# TUN7_Control.net
KiCad netlist of a schematic drawn in Altium Designer
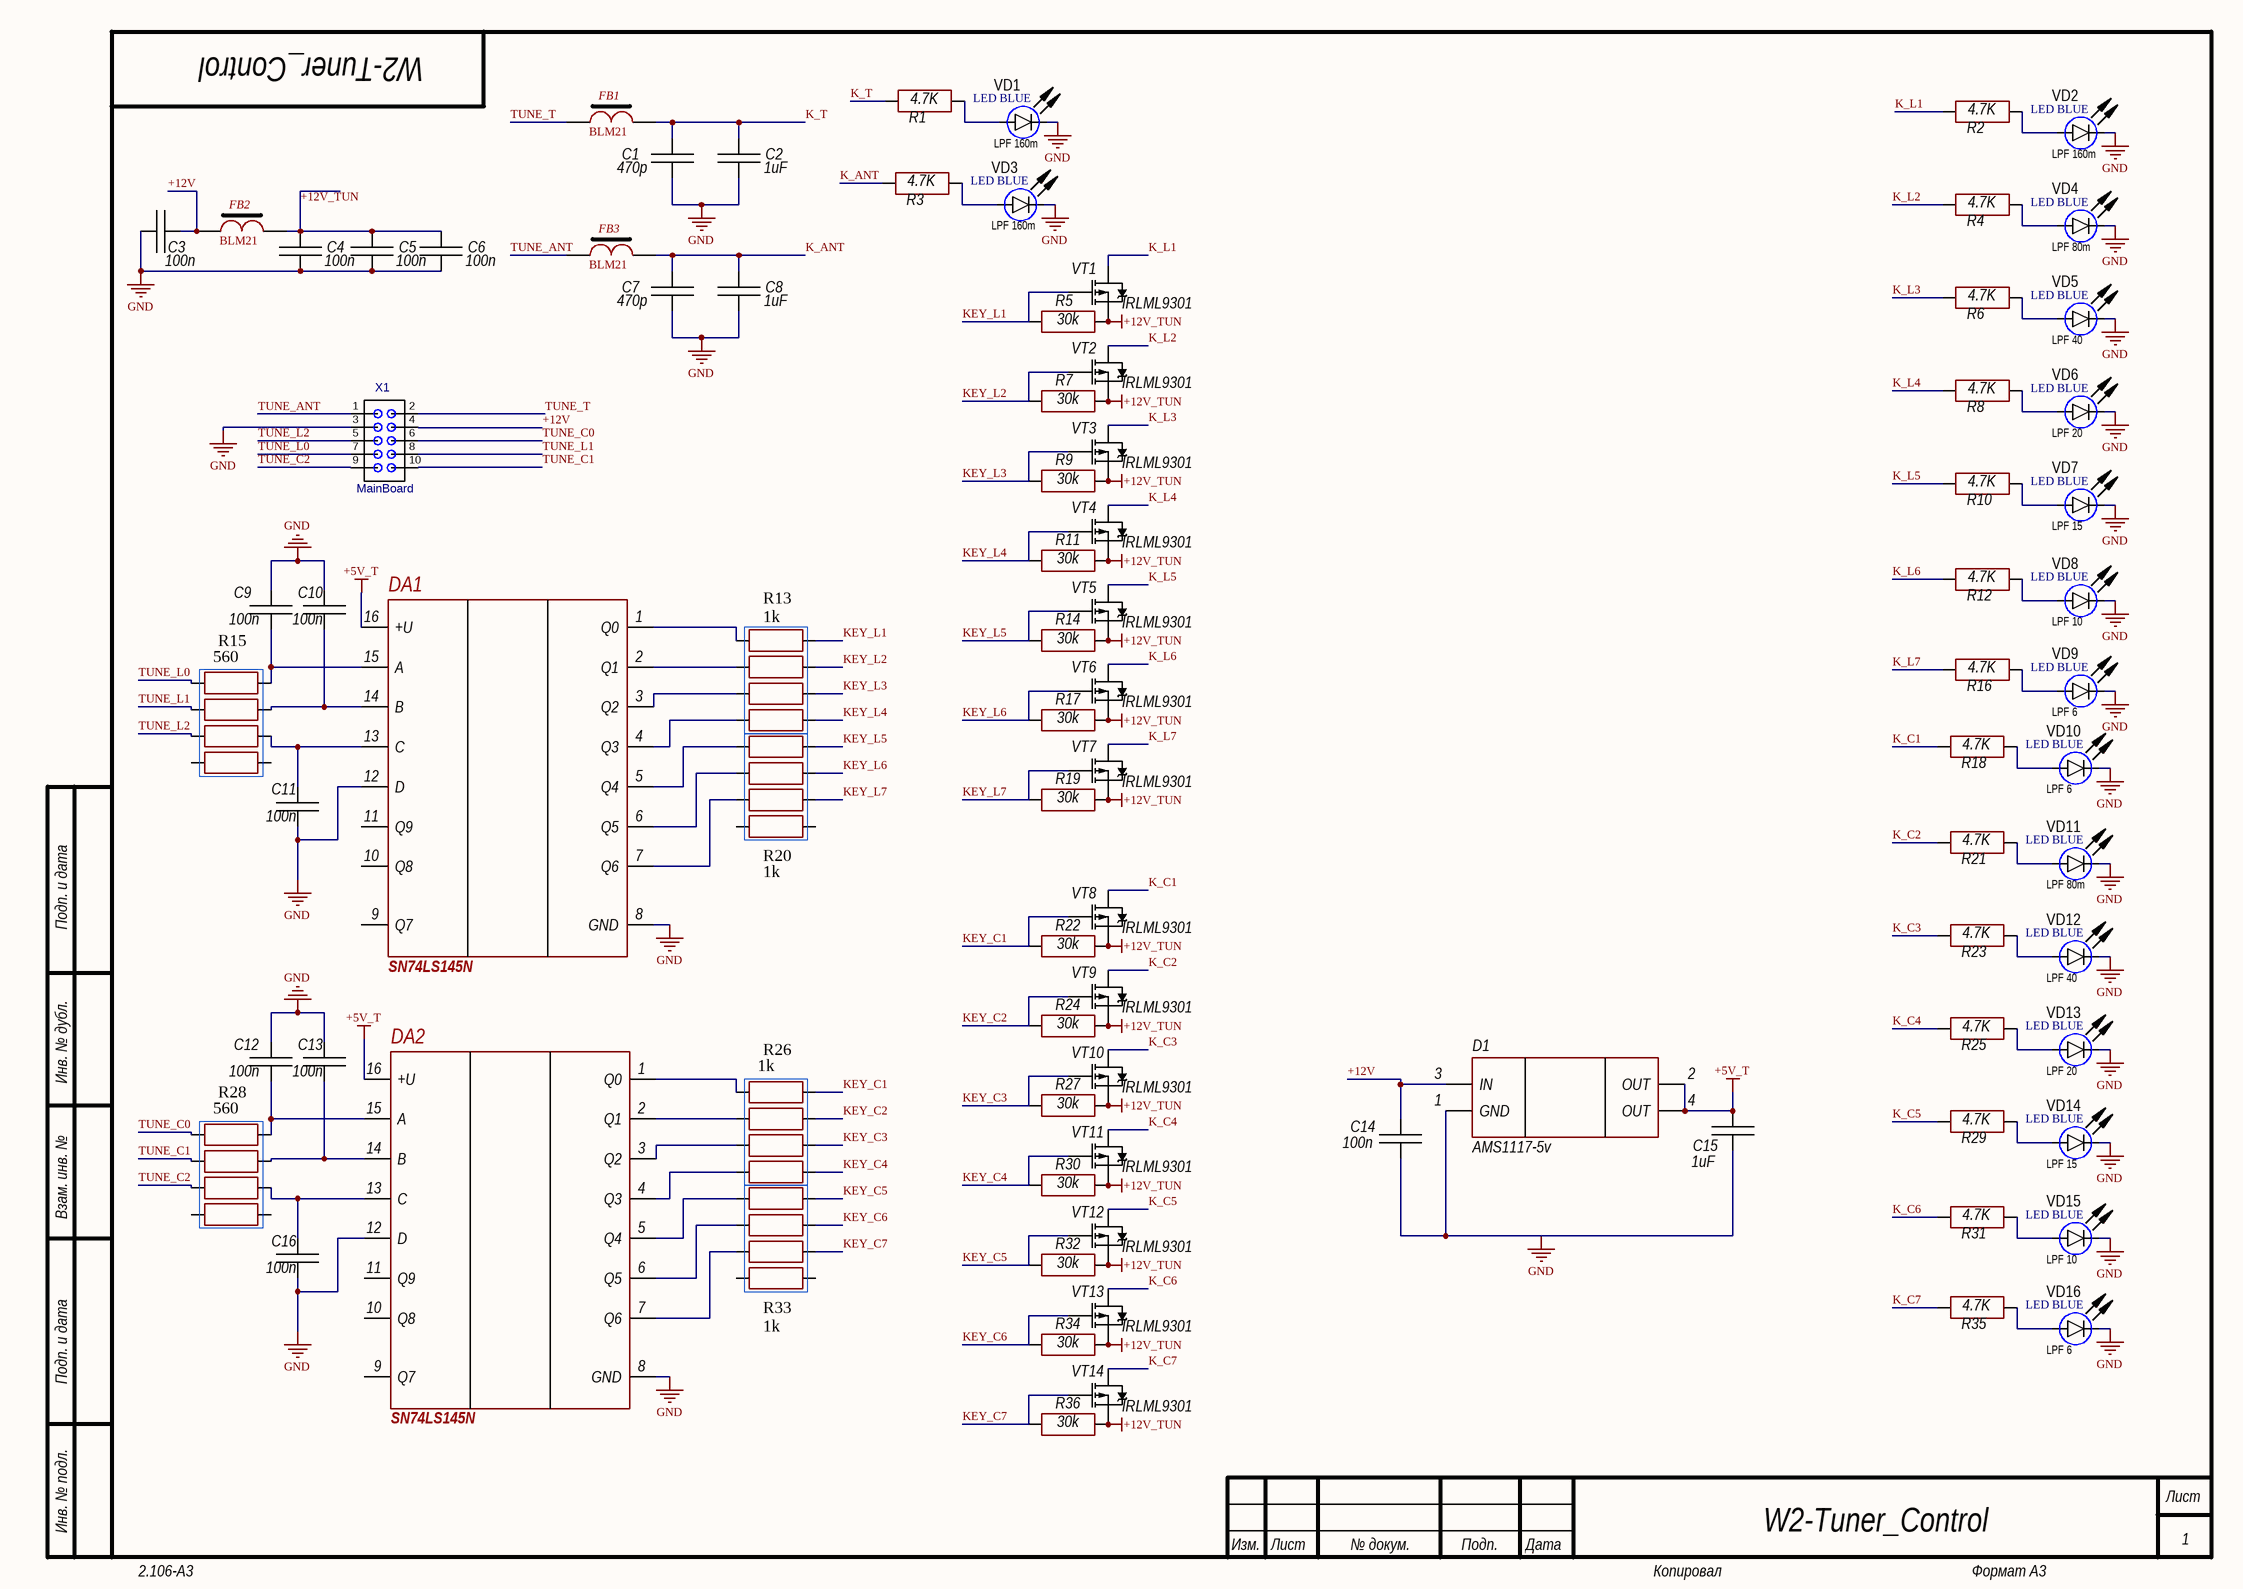
[diagram p0: TUN7_Control.SchDoc]

(export (version "E")
  (design (tool "Eeschema 10.0.6"))
  (components
    (comp (ref "C1")
      (value "470p")
      (footprint "standard:CH0805C")
      (libsource (lib "Discrete") (part "Capacitor"))
    )
    (comp (ref "C2")
      (value "1uF")
      (footprint "standard:CH0805C")
      (libsource (lib "Discrete") (part "Capacitor"))
    )
    (comp (ref "C3")
      (value "100n")
      (footprint "standard:CH0805C")
      (libsource (lib "Discrete") (part "Capacitor"))
    )
    (comp (ref "C4")
      (value "100n")
      (footprint "standard:CH0805C")
      (libsource (lib "Discrete") (part "Capacitor"))
    )
    (comp (ref "C5") (value "100n") (footprint "standard:CH0805C") (libsource (lib "") (part "Capacitor_1")))
    (comp (ref "C6") (value "100n") (footprint "standard:CH0805C") (libsource (lib "") (part "Capacitor_1")))
    (comp (ref "C7")
      (value "470p")
      (footprint "standard:CH0805C")
      (libsource (lib "Discrete") (part "Capacitor"))
    )
    (comp (ref "C8")
      (value "1uF")
      (footprint "standard:CH0805C")
      (libsource (lib "Discrete") (part "Capacitor"))
    )
    (comp (ref "C9")
      (value "100n")
      (footprint "standard:CH0805C")
      (libsource (lib "Discrete") (part "Capacitor"))
    )
    (comp (ref "C10")
      (value "100n")
      (footprint "standard:CH0805C")
      (libsource (lib "Discrete") (part "Capacitor"))
    )
    (comp (ref "C11")
      (value "100n")
      (footprint "standard:CH0805C")
      (libsource (lib "Discrete") (part "Capacitor"))
    )
    (comp (ref "C12")
      (value "100n")
      (footprint "standard:CH0805C")
      (libsource (lib "Discrete") (part "Capacitor"))
    )
    (comp (ref "C13")
      (value "100n")
      (footprint "standard:CH0805C")
      (libsource (lib "Discrete") (part "Capacitor"))
    )
    (comp (ref "C14")
      (value "100n")
      (footprint "standard:CH0805C")
      (libsource (lib "Discrete") (part "Capacitor"))
    )
    (comp (ref "C15")
      (value "1uF")
      (footprint "standard:CH0805C")
      (libsource (lib "Discrete") (part "Capacitor"))
    )
    (comp (ref "C16")
      (value "100n")
      (footprint "standard:CH0805C")
      (libsource (lib "Discrete") (part "Capacitor"))
    )
    (comp (ref "D1")
      (value "AMS1117-5v")
      (footprint "standard:SOT223")
      (description "LDO")
      (fields (field (name "MANUFACTURER") "ON Semiconductor"))
      (libsource (lib "Power Supplies") (part "NCP1117LPST50T3G"))
    )
    (comp (ref "DA1")
      (value "SN74LS145N")
      (footprint "16-SOP")
      (libsource (lib "Digital") (part "SN74LS145N"))
    )
    (comp (ref "DA2") (value "SN74LS145N") (footprint "16-SOP") (libsource (lib "") (part "SN74LS145N_1")))
    (comp (ref "FB1") (value "BLM21") (footprint "CH0805L") (libsource (lib "Discrete") (part "FB-1")))
    (comp (ref "FB2") (value "BLM21") (footprint "CH0805L") (libsource (lib "Discrete") (part "FB-1")))
    (comp (ref "FB3") (value "BLM21") (footprint "CH0805L") (libsource (lib "Discrete") (part "FB-1")))
    (comp (ref "R1")
      (value "4.7K")
      (footprint "standard:CH0805R")
      (libsource (lib "Discrete") (part "Resistor"))
    )
    (comp (ref "R2")
      (value "4.7K")
      (footprint "standard:CH0805R")
      (libsource (lib "Discrete") (part "Resistor"))
    )
    (comp (ref "R3")
      (value "4.7K")
      (footprint "standard:CH0805R")
      (libsource (lib "Discrete") (part "Resistor"))
    )
    (comp (ref "R4")
      (value "4.7K")
      (footprint "standard:CH0805R")
      (libsource (lib "Discrete") (part "Resistor"))
    )
    (comp (ref "R5")
      (value "30k")
      (footprint "standard:CH0805R")
      (libsource (lib "Discrete") (part "Resistor"))
    )
    (comp (ref "R6")
      (value "4.7K")
      (footprint "standard:CH0805R")
      (libsource (lib "Discrete") (part "Resistor"))
    )
    (comp (ref "R7")
      (value "30k")
      (footprint "standard:CH0805R")
      (libsource (lib "Discrete") (part "Resistor"))
    )
    (comp (ref "R8")
      (value "4.7K")
      (footprint "standard:CH0805R")
      (libsource (lib "Discrete") (part "Resistor"))
    )
    (comp (ref "R9")
      (value "30k")
      (footprint "standard:CH0805R")
      (libsource (lib "Discrete") (part "Resistor"))
    )
    (comp (ref "R10")
      (value "4.7K")
      (footprint "standard:CH0805R")
      (libsource (lib "Discrete") (part "Resistor"))
    )
    (comp (ref "R11")
      (value "30k")
      (footprint "standard:CH0805R")
      (libsource (lib "Discrete") (part "Resistor"))
    )
    (comp (ref "R12")
      (value "4.7K")
      (footprint "standard:CH0805R")
      (libsource (lib "Discrete") (part "Resistor"))
    )
    (comp (ref "R13") (value "1k") (footprint "CAT16") (libsource (lib "Discrete") (part "CAT10-0804")))
    (comp (ref "R14")
      (value "30k")
      (footprint "standard:CH0805R")
      (libsource (lib "Discrete") (part "Resistor"))
    )
    (comp (ref "R15") (value "560") (footprint "CAT16") (libsource (lib "Discrete") (part "CAT10-0804")))
    (comp (ref "R16")
      (value "4.7K")
      (footprint "standard:CH0805R")
      (libsource (lib "Discrete") (part "Resistor"))
    )
    (comp (ref "R17")
      (value "30k")
      (footprint "standard:CH0805R")
      (libsource (lib "Discrete") (part "Resistor"))
    )
    (comp (ref "R18")
      (value "4.7K")
      (footprint "standard:CH0805R")
      (libsource (lib "Discrete") (part "Resistor"))
    )
    (comp (ref "R19")
      (value "30k")
      (footprint "standard:CH0805R")
      (libsource (lib "Discrete") (part "Resistor"))
    )
    (comp (ref "R20") (value "1k") (footprint "CAT16") (libsource (lib "Discrete") (part "CAT10-0804")))
    (comp (ref "R21")
      (value "4.7K")
      (footprint "standard:CH0805R")
      (libsource (lib "Discrete") (part "Resistor"))
    )
    (comp (ref "R22")
      (value "30k")
      (footprint "standard:CH0805R")
      (libsource (lib "Discrete") (part "Resistor"))
    )
    (comp (ref "R23")
      (value "4.7K")
      (footprint "standard:CH0805R")
      (libsource (lib "Discrete") (part "Resistor"))
    )
    (comp (ref "R24")
      (value "30k")
      (footprint "standard:CH0805R")
      (libsource (lib "Discrete") (part "Resistor"))
    )
    (comp (ref "R25")
      (value "4.7K")
      (footprint "standard:CH0805R")
      (libsource (lib "Discrete") (part "Resistor"))
    )
    (comp (ref "R26") (value "1k") (footprint "CAT16") (libsource (lib "Discrete") (part "CAT10-0804")))
    (comp (ref "R27")
      (value "30k")
      (footprint "standard:CH0805R")
      (libsource (lib "Discrete") (part "Resistor"))
    )
    (comp (ref "R28") (value "560") (footprint "CAT16") (libsource (lib "Discrete") (part "CAT10-0804")))
    (comp (ref "R29")
      (value "4.7K")
      (footprint "standard:CH0805R")
      (libsource (lib "Discrete") (part "Resistor"))
    )
    (comp (ref "R30")
      (value "30k")
      (footprint "standard:CH0805R")
      (libsource (lib "Discrete") (part "Resistor"))
    )
    (comp (ref "R31")
      (value "4.7K")
      (footprint "standard:CH0805R")
      (libsource (lib "Discrete") (part "Resistor"))
    )
    (comp (ref "R32")
      (value "30k")
      (footprint "standard:CH0805R")
      (libsource (lib "Discrete") (part "Resistor"))
    )
    (comp (ref "R33") (value "1k") (footprint "CAT16") (libsource (lib "Discrete") (part "CAT10-0804")))
    (comp (ref "R34")
      (value "30k")
      (footprint "standard:CH0805R")
      (libsource (lib "Discrete") (part "Resistor"))
    )
    (comp (ref "R35")
      (value "4.7K")
      (footprint "standard:CH0805R")
      (libsource (lib "Discrete") (part "Resistor"))
    )
    (comp (ref "R36")
      (value "30k")
      (footprint "standard:CH0805R")
      (libsource (lib "Discrete") (part "Resistor"))
    )
    (comp (ref "VD1")
      (value "LED BLUE")
      (footprint "StandardCase:LED: 0805B")
      (fields
        (field (name "VALUEMANUFACTURERPARTNUMBER") "LED, *, *, *, -55...+150°C")
        (field (name "COLOR") "LPF 160m")
      )
      (libsource (lib "Diode") (part "LED_single"))
    )
    (comp (ref "VD2")
      (value "LED BLUE")
      (footprint "StandardCase:LED: 0805B")
      (fields
        (field (name "VALUEMANUFACTURERPARTNUMBER") "LED, *, *, *, -55...+150°C")
        (field (name "COLOR") "LPF 160m")
      )
      (libsource (lib "Diode") (part "LED_single"))
    )
    (comp (ref "VD3")
      (value "LED BLUE")
      (footprint "StandardCase:LED: 0805B")
      (fields
        (field (name "VALUEMANUFACTURERPARTNUMBER") "LED, *, *, *, -55...+150°C")
        (field (name "COLOR") "LPF 160m")
      )
      (libsource (lib "Diode") (part "LED_single"))
    )
    (comp (ref "VD4")
      (value "LED BLUE")
      (footprint "StandardCase:LED: 0805B")
      (fields
        (field (name "VALUEMANUFACTURERPARTNUMBER") "LED, *, *, *, -55...+150°C")
        (field (name "COLOR") "LPF 80m")
      )
      (libsource (lib "Diode") (part "LED_single"))
    )
    (comp (ref "VD5")
      (value "LED BLUE")
      (footprint "StandardCase:LED: 0805B")
      (fields
        (field (name "VALUEMANUFACTURERPARTNUMBER") "LED, *, *, *, -55...+150°C")
        (field (name "COLOR") "LPF 40")
      )
      (libsource (lib "Diode") (part "LED_single"))
    )
    (comp (ref "VD6")
      (value "LED BLUE")
      (footprint "StandardCase:LED: 0805B")
      (fields
        (field (name "VALUEMANUFACTURERPARTNUMBER") "LED, *, *, *, -55...+150°C")
        (field (name "COLOR") "LPF 20")
      )
      (libsource (lib "Diode") (part "LED_single"))
    )
    (comp (ref "VD7")
      (value "LED BLUE")
      (footprint "StandardCase:LED: 0805B")
      (fields
        (field (name "VALUEMANUFACTURERPARTNUMBER") "LED, *, *, *, -55...+150°C")
        (field (name "COLOR") "LPF 15")
      )
      (libsource (lib "Diode") (part "LED_single"))
    )
    (comp (ref "VD8")
      (value "LED BLUE")
      (footprint "StandardCase:LED: 0805B")
      (fields
        (field (name "VALUEMANUFACTURERPARTNUMBER") "LED, *, *, *, -55...+150°C")
        (field (name "COLOR") "LPF 10")
      )
      (libsource (lib "Diode") (part "LED_single"))
    )
    (comp (ref "VD9")
      (value "LED BLUE")
      (footprint "StandardCase:LED: 0805B")
      (fields
        (field (name "VALUEMANUFACTURERPARTNUMBER") "LED, *, *, *, -55...+150°C")
        (field (name "COLOR") "LPF 6")
      )
      (libsource (lib "Diode") (part "LED_single"))
    )
    (comp (ref "VD10")
      (value "LED BLUE")
      (footprint "StandardCase:LED: 0805B")
      (fields
        (field (name "VALUEMANUFACTURERPARTNUMBER") "LED, *, *, *, -55...+150°C")
        (field (name "COLOR") "LPF 6")
      )
      (libsource (lib "Diode") (part "LED_single"))
    )
    (comp (ref "VD11")
      (value "LED BLUE")
      (footprint "StandardCase:LED: 0805B")
      (fields
        (field (name "VALUEMANUFACTURERPARTNUMBER") "LED, *, *, *, -55...+150°C")
        (field (name "COLOR") "LPF 80m")
      )
      (libsource (lib "Diode") (part "LED_single"))
    )
    (comp (ref "VD12")
      (value "LED BLUE")
      (footprint "StandardCase:LED: 0805B")
      (fields
        (field (name "VALUEMANUFACTURERPARTNUMBER") "LED, *, *, *, -55...+150°C")
        (field (name "COLOR") "LPF 40")
      )
      (libsource (lib "Diode") (part "LED_single"))
    )
    (comp (ref "VD13")
      (value "LED BLUE")
      (footprint "StandardCase:LED: 0805B")
      (fields
        (field (name "VALUEMANUFACTURERPARTNUMBER") "LED, *, *, *, -55...+150°C")
        (field (name "COLOR") "LPF 20")
      )
      (libsource (lib "Diode") (part "LED_single"))
    )
    (comp (ref "VD14")
      (value "LED BLUE")
      (footprint "StandardCase:LED: 0805B")
      (fields
        (field (name "VALUEMANUFACTURERPARTNUMBER") "LED, *, *, *, -55...+150°C")
        (field (name "COLOR") "LPF 15")
      )
      (libsource (lib "Diode") (part "LED_single"))
    )
    (comp (ref "VD15")
      (value "LED BLUE")
      (footprint "StandardCase:LED: 0805B")
      (fields
        (field (name "VALUEMANUFACTURERPARTNUMBER") "LED, *, *, *, -55...+150°C")
        (field (name "COLOR") "LPF 10")
      )
      (libsource (lib "Diode") (part "LED_single"))
    )
    (comp (ref "VD16")
      (value "LED BLUE")
      (footprint "StandardCase:LED: 0805B")
      (fields
        (field (name "VALUEMANUFACTURERPARTNUMBER") "LED, *, *, *, -55...+150°C")
        (field (name "COLOR") "LPF 6")
      )
      (libsource (lib "Diode") (part "LED_single"))
    )
    (comp (ref "VT1")
      (value "IRLML9301")
      (footprint "standard:SOT23_132")
      (description "Mosfet")
      (libsource (lib "Transistor") (part "IRLML9301"))
    )
    (comp (ref "VT2")
      (value "IRLML9301")
      (footprint "standard:SOT23_132")
      (description "Mosfet")
      (libsource (lib "Transistor") (part "IRLML9301"))
    )
    (comp (ref "VT3")
      (value "IRLML9301")
      (footprint "standard:SOT23_132")
      (description "Mosfet")
      (libsource (lib "Transistor") (part "IRLML9301"))
    )
    (comp (ref "VT4")
      (value "IRLML9301")
      (footprint "standard:SOT23_132")
      (description "Mosfet")
      (libsource (lib "Transistor") (part "IRLML9301"))
    )
    (comp (ref "VT5")
      (value "IRLML9301")
      (footprint "standard:SOT23_132")
      (description "Mosfet")
      (libsource (lib "Transistor") (part "IRLML9301"))
    )
    (comp (ref "VT6")
      (value "IRLML9301")
      (footprint "standard:SOT23_132")
      (description "Mosfet")
      (libsource (lib "Transistor") (part "IRLML9301"))
    )
    (comp (ref "VT7")
      (value "IRLML9301")
      (footprint "standard:SOT23_132")
      (description "Mosfet")
      (libsource (lib "Transistor") (part "IRLML9301"))
    )
    (comp (ref "VT8")
      (value "IRLML9301")
      (footprint "standard:SOT23_132")
      (description "Mosfet")
      (libsource (lib "Transistor") (part "IRLML9301"))
    )
    (comp (ref "VT9")
      (value "IRLML9301")
      (footprint "standard:SOT23_132")
      (description "Mosfet")
      (libsource (lib "Transistor") (part "IRLML9301"))
    )
    (comp (ref "VT10")
      (value "IRLML9301")
      (footprint "standard:SOT23_132")
      (description "Mosfet")
      (libsource (lib "Transistor") (part "IRLML9301"))
    )
    (comp (ref "VT11")
      (value "IRLML9301")
      (footprint "standard:SOT23_132")
      (description "Mosfet")
      (libsource (lib "Transistor") (part "IRLML9301"))
    )
    (comp (ref "VT12")
      (value "IRLML9301")
      (footprint "standard:SOT23_132")
      (description "Mosfet")
      (libsource (lib "Transistor") (part "IRLML9301"))
    )
    (comp (ref "VT13")
      (value "IRLML9301")
      (footprint "standard:SOT23_132")
      (description "Mosfet")
      (libsource (lib "Transistor") (part "IRLML9301"))
    )
    (comp (ref "VT14")
      (value "IRLML9301")
      (footprint "standard:SOT23_132")
      (description "Mosfet")
      (libsource (lib "Transistor") (part "IRLML9301"))
    )
    (comp (ref "X1")
      (value "MainBoard")
      (footprint "CON: BH-10")
      (description "2*5 Pin")
      (libsource (lib "*") (part "IDC10"))
    )
  )
  (nets
    (net (code "1") (name "+5V_T") (class "Default")
      (node (ref "C15") (pin "2") (pinfunction "2_2") (pintype "power_in"))
      (node (ref "D1") (pin "2") (pinfunction "OUT_2") (pintype "passive"))
      (node (ref "D1") (pin "4") (pinfunction "OUT_4") (pintype "passive"))
      (node (ref "DA1") (pin "16") (pinfunction "+U_16") (pintype "passive"))
      (node (ref "DA2") (pin "16") (pinfunction "+U_16") (pintype "passive"))
    )
    (net (code "2") (name "+12V_TUN") (class "Default")
      (node (ref "C4") (pin "2") (pinfunction "2_2") (pintype "power_in"))
      (node (ref "C5") (pin "2") (pinfunction "2_2") (pintype "power_in"))
      (node (ref "C6") (pin "2") (pinfunction "2_2") (pintype "power_in"))
      (node (ref "FB2") (pin "1") (pinfunction "1_1") (pintype "passive"))
      (node (ref "R11") (pin "1") (pinfunction "1_1") (pintype "passive"))
      (node (ref "R14") (pin "1") (pinfunction "1_1") (pintype "passive"))
      (node (ref "R17") (pin "1") (pinfunction "1_1") (pintype "passive"))
      (node (ref "R19") (pin "1") (pinfunction "1_1") (pintype "passive"))
      (node (ref "R22") (pin "1") (pinfunction "1_1") (pintype "passive"))
      (node (ref "R24") (pin "1") (pinfunction "1_1") (pintype "passive"))
      (node (ref "R27") (pin "1") (pinfunction "1_1") (pintype "passive"))
      (node (ref "R30") (pin "1") (pinfunction "1_1") (pintype "passive"))
      (node (ref "R32") (pin "1") (pinfunction "1_1") (pintype "passive"))
      (node (ref "R34") (pin "1") (pinfunction "1_1") (pintype "passive"))
      (node (ref "R36") (pin "1") (pinfunction "1_1") (pintype "passive"))
      (node (ref "R5") (pin "1") (pinfunction "1_1") (pintype "passive"))
      (node (ref "R7") (pin "1") (pinfunction "1_1") (pintype "passive"))
      (node (ref "R9") (pin "1") (pinfunction "1_1") (pintype "passive"))
      (node (ref "VT1") (pin "2") (pinfunction "S_2") (pintype "passive"))
      (node (ref "VT10") (pin "2") (pinfunction "S_2") (pintype "passive"))
      (node (ref "VT11") (pin "2") (pinfunction "S_2") (pintype "passive"))
      (node (ref "VT12") (pin "2") (pinfunction "S_2") (pintype "passive"))
      (node (ref "VT13") (pin "2") (pinfunction "S_2") (pintype "passive"))
      (node (ref "VT14") (pin "2") (pinfunction "S_2") (pintype "passive"))
      (node (ref "VT2") (pin "2") (pinfunction "S_2") (pintype "passive"))
      (node (ref "VT3") (pin "2") (pinfunction "S_2") (pintype "passive"))
      (node (ref "VT4") (pin "2") (pinfunction "S_2") (pintype "passive"))
      (node (ref "VT5") (pin "2") (pinfunction "S_2") (pintype "passive"))
      (node (ref "VT6") (pin "2") (pinfunction "S_2") (pintype "passive"))
      (node (ref "VT7") (pin "2") (pinfunction "S_2") (pintype "passive"))
      (node (ref "VT8") (pin "2") (pinfunction "S_2") (pintype "passive"))
      (node (ref "VT9") (pin "2") (pinfunction "S_2") (pintype "passive"))
    )
    (net (code "3") (name "/+12V") (class "Default")
      (node (ref "C14") (pin "2") (pinfunction "2_2") (pintype "power_in"))
      (node (ref "C3") (pin "2") (pinfunction "2_2") (pintype "power_in"))
      (node (ref "D1") (pin "3") (pinfunction "IN_3") (pintype "power_in"))
      (node (ref "FB2") (pin "2") (pinfunction "2_2") (pintype "passive"))
      (node (ref "X1") (pin "4") (pinfunction "4_4") (pintype "passive"))
    )
    (net (code "4") (name "/KEY_C1") (class "Default")
      (node (ref "R22") (pin "2") (pinfunction "2_2") (pintype "passive"))
      (node (ref "R26") (pin "5") (pinfunction "5_5") (pintype "passive"))
      (node (ref "VT8") (pin "1") (pinfunction "G_1") (pintype "passive"))
    )
    (net (code "5") (name "/KEY_C2") (class "Default")
      (node (ref "R24") (pin "2") (pinfunction "2_2") (pintype "passive"))
      (node (ref "R26") (pin "6") (pinfunction "6_6") (pintype "passive"))
      (node (ref "VT9") (pin "1") (pinfunction "G_1") (pintype "passive"))
    )
    (net (code "6") (name "/KEY_C3") (class "Default")
      (node (ref "R26") (pin "7") (pinfunction "7_7") (pintype "passive"))
      (node (ref "R27") (pin "2") (pinfunction "2_2") (pintype "passive"))
      (node (ref "VT10") (pin "1") (pinfunction "G_1") (pintype "passive"))
    )
    (net (code "7") (name "/KEY_C4") (class "Default")
      (node (ref "R26") (pin "8") (pinfunction "8_8") (pintype "passive"))
      (node (ref "R30") (pin "2") (pinfunction "2_2") (pintype "passive"))
      (node (ref "VT11") (pin "1") (pinfunction "G_1") (pintype "passive"))
    )
    (net (code "8") (name "/KEY_C5") (class "Default")
      (node (ref "R32") (pin "2") (pinfunction "2_2") (pintype "passive"))
      (node (ref "R33") (pin "5") (pinfunction "5_5") (pintype "passive"))
      (node (ref "VT12") (pin "1") (pinfunction "G_1") (pintype "passive"))
    )
    (net (code "9") (name "/KEY_C6") (class "Default")
      (node (ref "R33") (pin "6") (pinfunction "6_6") (pintype "passive"))
      (node (ref "R34") (pin "2") (pinfunction "2_2") (pintype "passive"))
      (node (ref "VT13") (pin "1") (pinfunction "G_1") (pintype "passive"))
    )
    (net (code "10") (name "/KEY_C7") (class "Default")
      (node (ref "R33") (pin "7") (pinfunction "7_7") (pintype "passive"))
      (node (ref "R36") (pin "2") (pinfunction "2_2") (pintype "passive"))
      (node (ref "VT14") (pin "1") (pinfunction "G_1") (pintype "passive"))
    )
    (net (code "11") (name "/KEY_L1") (class "Default")
      (node (ref "R13") (pin "5") (pinfunction "5_5") (pintype "passive"))
      (node (ref "R5") (pin "2") (pinfunction "2_2") (pintype "passive"))
      (node (ref "VT1") (pin "1") (pinfunction "G_1") (pintype "passive"))
    )
    (net (code "12") (name "/KEY_L2") (class "Default")
      (node (ref "R13") (pin "6") (pinfunction "6_6") (pintype "passive"))
      (node (ref "R7") (pin "2") (pinfunction "2_2") (pintype "passive"))
      (node (ref "VT2") (pin "1") (pinfunction "G_1") (pintype "passive"))
    )
    (net (code "13") (name "/KEY_L3") (class "Default")
      (node (ref "R13") (pin "7") (pinfunction "7_7") (pintype "passive"))
      (node (ref "R9") (pin "2") (pinfunction "2_2") (pintype "passive"))
      (node (ref "VT3") (pin "1") (pinfunction "G_1") (pintype "passive"))
    )
    (net (code "14") (name "/KEY_L4") (class "Default")
      (node (ref "R11") (pin "2") (pinfunction "2_2") (pintype "passive"))
      (node (ref "R13") (pin "8") (pinfunction "8_8") (pintype "passive"))
      (node (ref "VT4") (pin "1") (pinfunction "G_1") (pintype "passive"))
    )
    (net (code "15") (name "/KEY_L5") (class "Default")
      (node (ref "R14") (pin "2") (pinfunction "2_2") (pintype "passive"))
      (node (ref "R20") (pin "5") (pinfunction "5_5") (pintype "passive"))
      (node (ref "VT5") (pin "1") (pinfunction "G_1") (pintype "passive"))
    )
    (net (code "16") (name "/KEY_L6") (class "Default")
      (node (ref "R17") (pin "2") (pinfunction "2_2") (pintype "passive"))
      (node (ref "R20") (pin "6") (pinfunction "6_6") (pintype "passive"))
      (node (ref "VT6") (pin "1") (pinfunction "G_1") (pintype "passive"))
    )
    (net (code "17") (name "/KEY_L7") (class "Default")
      (node (ref "R19") (pin "2") (pinfunction "2_2") (pintype "passive"))
      (node (ref "R20") (pin "7") (pinfunction "7_7") (pintype "passive"))
      (node (ref "VT7") (pin "1") (pinfunction "G_1") (pintype "passive"))
    )
    (net (code "18") (name "/K_ANT") (class "Default")
      (node (ref "C7") (pin "1") (pinfunction "1_1") (pintype "power_in"))
      (node (ref "C8") (pin "1") (pinfunction "1_1") (pintype "power_in"))
      (node (ref "FB3") (pin "1") (pinfunction "1_1") (pintype "passive"))
      (node (ref "R3") (pin "2") (pinfunction "2_2") (pintype "passive"))
    )
    (net (code "19") (name "/K_C1") (class "Default")
      (node (ref "R18") (pin "2") (pinfunction "2_2") (pintype "passive"))
      (node (ref "VT8") (pin "3") (pinfunction "D_3") (pintype "passive"))
    )
    (net (code "20") (name "/K_C2") (class "Default")
      (node (ref "R21") (pin "2") (pinfunction "2_2") (pintype "passive"))
      (node (ref "VT9") (pin "3") (pinfunction "D_3") (pintype "passive"))
    )
    (net (code "21") (name "/K_C3") (class "Default")
      (node (ref "R23") (pin "2") (pinfunction "2_2") (pintype "passive"))
      (node (ref "VT10") (pin "3") (pinfunction "D_3") (pintype "passive"))
    )
    (net (code "22") (name "/K_C4") (class "Default")
      (node (ref "R25") (pin "2") (pinfunction "2_2") (pintype "passive"))
      (node (ref "VT11") (pin "3") (pinfunction "D_3") (pintype "passive"))
    )
    (net (code "23") (name "/K_C5") (class "Default")
      (node (ref "R29") (pin "2") (pinfunction "2_2") (pintype "passive"))
      (node (ref "VT12") (pin "3") (pinfunction "D_3") (pintype "passive"))
    )
    (net (code "24") (name "/K_C6") (class "Default")
      (node (ref "R31") (pin "2") (pinfunction "2_2") (pintype "passive"))
      (node (ref "VT13") (pin "3") (pinfunction "D_3") (pintype "passive"))
    )
    (net (code "25") (name "/K_C7") (class "Default")
      (node (ref "R35") (pin "2") (pinfunction "2_2") (pintype "passive"))
      (node (ref "VT14") (pin "3") (pinfunction "D_3") (pintype "passive"))
    )
    (net (code "26") (name "/K_L1") (class "Default")
      (node (ref "R2") (pin "2") (pinfunction "2_2") (pintype "passive"))
      (node (ref "VT1") (pin "3") (pinfunction "D_3") (pintype "passive"))
    )
    (net (code "27") (name "/K_L2") (class "Default")
      (node (ref "R4") (pin "2") (pinfunction "2_2") (pintype "passive"))
      (node (ref "VT2") (pin "3") (pinfunction "D_3") (pintype "passive"))
    )
    (net (code "28") (name "/K_L3") (class "Default")
      (node (ref "R6") (pin "2") (pinfunction "2_2") (pintype "passive"))
      (node (ref "VT3") (pin "3") (pinfunction "D_3") (pintype "passive"))
    )
    (net (code "29") (name "/K_L4") (class "Default")
      (node (ref "R8") (pin "2") (pinfunction "2_2") (pintype "passive"))
      (node (ref "VT4") (pin "3") (pinfunction "D_3") (pintype "passive"))
    )
    (net (code "30") (name "/K_L5") (class "Default")
      (node (ref "R10") (pin "2") (pinfunction "2_2") (pintype "passive"))
      (node (ref "VT5") (pin "3") (pinfunction "D_3") (pintype "passive"))
    )
    (net (code "31") (name "/K_L6") (class "Default")
      (node (ref "R12") (pin "2") (pinfunction "2_2") (pintype "passive"))
      (node (ref "VT6") (pin "3") (pinfunction "D_3") (pintype "passive"))
    )
    (net (code "32") (name "/K_L7") (class "Default")
      (node (ref "R16") (pin "2") (pinfunction "2_2") (pintype "passive"))
      (node (ref "VT7") (pin "3") (pinfunction "D_3") (pintype "passive"))
    )
    (net (code "33") (name "/K_T") (class "Default")
      (node (ref "C1") (pin "1") (pinfunction "1_1") (pintype "power_in"))
      (node (ref "C2") (pin "1") (pinfunction "1_1") (pintype "power_in"))
      (node (ref "FB1") (pin "1") (pinfunction "1_1") (pintype "passive"))
      (node (ref "R1") (pin "2") (pinfunction "2_2") (pintype "passive"))
    )
    (net (code "34") (name "/TUNE_ANT") (class "Default")
      (node (ref "FB3") (pin "2") (pinfunction "2_2") (pintype "passive"))
      (node (ref "X1") (pin "1") (pinfunction "1_1") (pintype "passive"))
    )
    (net (code "35") (name "/TUNE_C0") (class "Default")
      (node (ref "R28") (pin "1") (pinfunction "1_1") (pintype "passive"))
      (node (ref "X1") (pin "6") (pinfunction "6_6") (pintype "passive"))
    )
    (net (code "36") (name "/TUNE_C1") (class "Default")
      (node (ref "R28") (pin "2") (pinfunction "2_2") (pintype "passive"))
      (node (ref "X1") (pin "10") (pinfunction "10_10") (pintype "passive"))
    )
    (net (code "37") (name "/TUNE_C2") (class "Default")
      (node (ref "R28") (pin "3") (pinfunction "3_3") (pintype "passive"))
      (node (ref "X1") (pin "9") (pinfunction "9_9") (pintype "passive"))
    )
    (net (code "38") (name "/TUNE_L0") (class "Default")
      (node (ref "R15") (pin "1") (pinfunction "1_1") (pintype "passive"))
      (node (ref "X1") (pin "7") (pinfunction "7_7") (pintype "passive"))
    )
    (net (code "39") (name "/TUNE_L1") (class "Default")
      (node (ref "R15") (pin "2") (pinfunction "2_2") (pintype "passive"))
      (node (ref "X1") (pin "8") (pinfunction "8_8") (pintype "passive"))
    )
    (net (code "40") (name "/TUNE_L2") (class "Default")
      (node (ref "R15") (pin "3") (pinfunction "3_3") (pintype "passive"))
      (node (ref "X1") (pin "5") (pinfunction "5_5") (pintype "passive"))
    )
    (net (code "41") (name "/TUNE_T") (class "Default")
      (node (ref "FB1") (pin "2") (pinfunction "2_2") (pintype "passive"))
      (node (ref "X1") (pin "2") (pinfunction "2_2") (pintype "passive"))
    )
    (net (code "42") (name "GND") (class "Default")
      (node (ref "C1") (pin "2") (pinfunction "2_2") (pintype "power_in"))
      (node (ref "C10") (pin "1") (pinfunction "1_1") (pintype "power_in"))
      (node (ref "C11") (pin "2") (pinfunction "2_2") (pintype "power_in"))
      (node (ref "C12") (pin "1") (pinfunction "1_1") (pintype "power_in"))
      (node (ref "C13") (pin "1") (pinfunction "1_1") (pintype "power_in"))
      (node (ref "C14") (pin "1") (pinfunction "1_1") (pintype "power_in"))
      (node (ref "C15") (pin "1") (pinfunction "1_1") (pintype "power_in"))
      (node (ref "C16") (pin "2") (pinfunction "2_2") (pintype "power_in"))
      (node (ref "C2") (pin "2") (pinfunction "2_2") (pintype "power_in"))
      (node (ref "C3") (pin "1") (pinfunction "1_1") (pintype "power_in"))
      (node (ref "C4") (pin "1") (pinfunction "1_1") (pintype "power_in"))
      (node (ref "C5") (pin "1") (pinfunction "1_1") (pintype "power_in"))
      (node (ref "C6") (pin "1") (pinfunction "1_1") (pintype "power_in"))
      (node (ref "C7") (pin "2") (pinfunction "2_2") (pintype "power_in"))
      (node (ref "C8") (pin "2") (pinfunction "2_2") (pintype "power_in"))
      (node (ref "C9") (pin "1") (pinfunction "1_1") (pintype "power_in"))
      (node (ref "D1") (pin "1") (pinfunction "GND_1") (pintype "passive"))
      (node (ref "DA1") (pin "12") (pinfunction "D_12") (pintype "passive"))
      (node (ref "DA1") (pin "8") (pinfunction "GND_8") (pintype "passive"))
      (node (ref "DA2") (pin "12") (pinfunction "D_12") (pintype "passive"))
      (node (ref "DA2") (pin "8") (pinfunction "GND_8") (pintype "passive"))
      (node (ref "VD1") (pin "2") (pinfunction "C_2") (pintype "passive"))
      (node (ref "VD10") (pin "2") (pinfunction "C_2") (pintype "passive"))
      (node (ref "VD11") (pin "2") (pinfunction "C_2") (pintype "passive"))
      (node (ref "VD12") (pin "2") (pinfunction "C_2") (pintype "passive"))
      (node (ref "VD13") (pin "2") (pinfunction "C_2") (pintype "passive"))
      (node (ref "VD14") (pin "2") (pinfunction "C_2") (pintype "passive"))
      (node (ref "VD15") (pin "2") (pinfunction "C_2") (pintype "passive"))
      (node (ref "VD16") (pin "2") (pinfunction "C_2") (pintype "passive"))
      (node (ref "VD2") (pin "2") (pinfunction "C_2") (pintype "passive"))
      (node (ref "VD3") (pin "2") (pinfunction "C_2") (pintype "passive"))
      (node (ref "VD4") (pin "2") (pinfunction "C_2") (pintype "passive"))
      (node (ref "VD5") (pin "2") (pinfunction "C_2") (pintype "passive"))
      (node (ref "VD6") (pin "2") (pinfunction "C_2") (pintype "passive"))
      (node (ref "VD7") (pin "2") (pinfunction "C_2") (pintype "passive"))
      (node (ref "VD8") (pin "2") (pinfunction "C_2") (pintype "passive"))
      (node (ref "VD9") (pin "2") (pinfunction "C_2") (pintype "passive"))
      (node (ref "X1") (pin "3") (pinfunction "3_3") (pintype "passive"))
    )
    (net (code "43") (name "Net-(DA1-A)") (class "Default")
      (node (ref "C9") (pin "2") (pinfunction "2_2") (pintype "power_in"))
      (node (ref "DA1") (pin "15") (pinfunction "A_15") (pintype "passive"))
      (node (ref "R15") (pin "5") (pinfunction "5_5") (pintype "passive"))
    )
    (net (code "44") (name "Net-(DA1-B)") (class "Default")
      (node (ref "C10") (pin "2") (pinfunction "2_2") (pintype "power_in"))
      (node (ref "DA1") (pin "14") (pinfunction "B_14") (pintype "passive"))
      (node (ref "R15") (pin "6") (pinfunction "6_6") (pintype "passive"))
    )
    (net (code "45") (name "Net-(DA1-C)") (class "Default")
      (node (ref "C11") (pin "1") (pinfunction "1_1") (pintype "power_in"))
      (node (ref "DA1") (pin "13") (pinfunction "C_13") (pintype "passive"))
      (node (ref "R15") (pin "7") (pinfunction "7_7") (pintype "passive"))
    )
    (net (code "46") (name "Net-(DA1-Q0)") (class "Default")
      (node (ref "DA1") (pin "1") (pinfunction "Q0_1") (pintype "passive"))
      (node (ref "R13") (pin "1") (pinfunction "1_1") (pintype "passive"))
    )
    (net (code "47") (name "Net-(DA1-Q1)") (class "Default")
      (node (ref "DA1") (pin "2") (pinfunction "Q1_2") (pintype "passive"))
      (node (ref "R13") (pin "2") (pinfunction "2_2") (pintype "passive"))
    )
    (net (code "48") (name "Net-(DA1-Q2)") (class "Default")
      (node (ref "DA1") (pin "3") (pinfunction "Q2_3") (pintype "passive"))
      (node (ref "R13") (pin "3") (pinfunction "3_3") (pintype "passive"))
    )
    (net (code "49") (name "Net-(DA1-Q3)") (class "Default")
      (node (ref "DA1") (pin "4") (pinfunction "Q3_4") (pintype "passive"))
      (node (ref "R13") (pin "4") (pinfunction "4_4") (pintype "passive"))
    )
    (net (code "50") (name "Net-(DA1-Q4)") (class "Default")
      (node (ref "DA1") (pin "5") (pinfunction "Q4_5") (pintype "passive"))
      (node (ref "R20") (pin "1") (pinfunction "1_1") (pintype "passive"))
    )
    (net (code "51") (name "Net-(DA1-Q5)") (class "Default")
      (node (ref "DA1") (pin "6") (pinfunction "Q5_6") (pintype "passive"))
      (node (ref "R20") (pin "2") (pinfunction "2_2") (pintype "passive"))
    )
    (net (code "52") (name "Net-(DA1-Q6)") (class "Default")
      (node (ref "DA1") (pin "7") (pinfunction "Q6_7") (pintype "passive"))
      (node (ref "R20") (pin "3") (pinfunction "3_3") (pintype "passive"))
    )
    (net (code "53") (name "Net-(DA2-A)") (class "Default")
      (node (ref "C12") (pin "2") (pinfunction "2_2") (pintype "power_in"))
      (node (ref "DA2") (pin "15") (pinfunction "A_15") (pintype "passive"))
      (node (ref "R28") (pin "5") (pinfunction "5_5") (pintype "passive"))
    )
    (net (code "54") (name "Net-(DA2-B)") (class "Default")
      (node (ref "C13") (pin "2") (pinfunction "2_2") (pintype "power_in"))
      (node (ref "DA2") (pin "14") (pinfunction "B_14") (pintype "passive"))
      (node (ref "R28") (pin "6") (pinfunction "6_6") (pintype "passive"))
    )
    (net (code "55") (name "Net-(DA2-C)") (class "Default")
      (node (ref "C16") (pin "1") (pinfunction "1_1") (pintype "power_in"))
      (node (ref "DA2") (pin "13") (pinfunction "C_13") (pintype "passive"))
      (node (ref "R28") (pin "7") (pinfunction "7_7") (pintype "passive"))
    )
    (net (code "56") (name "Net-(DA2-Q0)") (class "Default")
      (node (ref "DA2") (pin "1") (pinfunction "Q0_1") (pintype "passive"))
      (node (ref "R26") (pin "1") (pinfunction "1_1") (pintype "passive"))
    )
    (net (code "57") (name "Net-(DA2-Q1)") (class "Default")
      (node (ref "DA2") (pin "2") (pinfunction "Q1_2") (pintype "passive"))
      (node (ref "R26") (pin "2") (pinfunction "2_2") (pintype "passive"))
    )
    (net (code "58") (name "Net-(DA2-Q2)") (class "Default")
      (node (ref "DA2") (pin "3") (pinfunction "Q2_3") (pintype "passive"))
      (node (ref "R26") (pin "3") (pinfunction "3_3") (pintype "passive"))
    )
    (net (code "59") (name "Net-(DA2-Q3)") (class "Default")
      (node (ref "DA2") (pin "4") (pinfunction "Q3_4") (pintype "passive"))
      (node (ref "R26") (pin "4") (pinfunction "4_4") (pintype "passive"))
    )
    (net (code "60") (name "Net-(DA2-Q4)") (class "Default")
      (node (ref "DA2") (pin "5") (pinfunction "Q4_5") (pintype "passive"))
      (node (ref "R33") (pin "1") (pinfunction "1_1") (pintype "passive"))
    )
    (net (code "61") (name "Net-(DA2-Q5)") (class "Default")
      (node (ref "DA2") (pin "6") (pinfunction "Q5_6") (pintype "passive"))
      (node (ref "R33") (pin "2") (pinfunction "2_2") (pintype "passive"))
    )
    (net (code "62") (name "Net-(DA2-Q6)") (class "Default")
      (node (ref "DA2") (pin "7") (pinfunction "Q6_7") (pintype "passive"))
      (node (ref "R33") (pin "3") (pinfunction "3_3") (pintype "passive"))
    )
    (net (code "63") (name "Net-(VD1-A)") (class "Default")
      (node (ref "R1") (pin "1") (pinfunction "1_1") (pintype "passive"))
      (node (ref "VD1") (pin "1") (pinfunction "A_1") (pintype "passive"))
    )
    (net (code "64") (name "Net-(VD2-A)") (class "Default")
      (node (ref "R2") (pin "1") (pinfunction "1_1") (pintype "passive"))
      (node (ref "VD2") (pin "1") (pinfunction "A_1") (pintype "passive"))
    )
    (net (code "65") (name "Net-(VD3-A)") (class "Default")
      (node (ref "R3") (pin "1") (pinfunction "1_1") (pintype "passive"))
      (node (ref "VD3") (pin "1") (pinfunction "A_1") (pintype "passive"))
    )
    (net (code "66") (name "Net-(VD4-A)") (class "Default")
      (node (ref "R4") (pin "1") (pinfunction "1_1") (pintype "passive"))
      (node (ref "VD4") (pin "1") (pinfunction "A_1") (pintype "passive"))
    )
    (net (code "67") (name "Net-(VD5-A)") (class "Default")
      (node (ref "R6") (pin "1") (pinfunction "1_1") (pintype "passive"))
      (node (ref "VD5") (pin "1") (pinfunction "A_1") (pintype "passive"))
    )
    (net (code "68") (name "Net-(VD6-A)") (class "Default")
      (node (ref "R8") (pin "1") (pinfunction "1_1") (pintype "passive"))
      (node (ref "VD6") (pin "1") (pinfunction "A_1") (pintype "passive"))
    )
    (net (code "69") (name "Net-(VD7-A)") (class "Default")
      (node (ref "R10") (pin "1") (pinfunction "1_1") (pintype "passive"))
      (node (ref "VD7") (pin "1") (pinfunction "A_1") (pintype "passive"))
    )
    (net (code "70") (name "Net-(VD8-A)") (class "Default")
      (node (ref "R12") (pin "1") (pinfunction "1_1") (pintype "passive"))
      (node (ref "VD8") (pin "1") (pinfunction "A_1") (pintype "passive"))
    )
    (net (code "71") (name "Net-(VD9-A)") (class "Default")
      (node (ref "R16") (pin "1") (pinfunction "1_1") (pintype "passive"))
      (node (ref "VD9") (pin "1") (pinfunction "A_1") (pintype "passive"))
    )
    (net (code "72") (name "Net-(VD10-A)") (class "Default")
      (node (ref "R18") (pin "1") (pinfunction "1_1") (pintype "passive"))
      (node (ref "VD10") (pin "1") (pinfunction "A_1") (pintype "passive"))
    )
    (net (code "73") (name "Net-(VD11-A)") (class "Default")
      (node (ref "R21") (pin "1") (pinfunction "1_1") (pintype "passive"))
      (node (ref "VD11") (pin "1") (pinfunction "A_1") (pintype "passive"))
    )
    (net (code "74") (name "Net-(VD12-A)") (class "Default")
      (node (ref "R23") (pin "1") (pinfunction "1_1") (pintype "passive"))
      (node (ref "VD12") (pin "1") (pinfunction "A_1") (pintype "passive"))
    )
    (net (code "75") (name "Net-(VD13-A)") (class "Default")
      (node (ref "R25") (pin "1") (pinfunction "1_1") (pintype "passive"))
      (node (ref "VD13") (pin "1") (pinfunction "A_1") (pintype "passive"))
    )
    (net (code "76") (name "Net-(VD14-A)") (class "Default")
      (node (ref "R29") (pin "1") (pinfunction "1_1") (pintype "passive"))
      (node (ref "VD14") (pin "1") (pinfunction "A_1") (pintype "passive"))
    )
    (net (code "77") (name "Net-(VD15-A)") (class "Default")
      (node (ref "R31") (pin "1") (pinfunction "1_1") (pintype "passive"))
      (node (ref "VD15") (pin "1") (pinfunction "A_1") (pintype "passive"))
    )
    (net (code "78") (name "Net-(VD16-A)") (class "Default")
      (node (ref "R35") (pin "1") (pinfunction "1_1") (pintype "passive"))
      (node (ref "VD16") (pin "1") (pinfunction "A_1") (pintype "passive"))
    )
    (net (code "79") (name "unconnected-(DA1-Q7-Pad9)") (class "Default")
      (node (ref "DA1") (pin "9") (pinfunction "Q7_9") (pintype "passive"))
    )
    (net (code "80") (name "unconnected-(DA1-Q8-Pad10)") (class "Default")
      (node (ref "DA1") (pin "10") (pinfunction "Q8_10") (pintype "passive"))
    )
    (net (code "81") (name "unconnected-(DA1-Q9-Pad11)") (class "Default")
      (node (ref "DA1") (pin "11") (pinfunction "Q9_11") (pintype "passive"))
    )
    (net (code "82") (name "unconnected-(DA2-Q7-Pad9)") (class "Default")
      (node (ref "DA2") (pin "9") (pinfunction "Q7_9") (pintype "passive"))
    )
    (net (code "83") (name "unconnected-(DA2-Q8-Pad10)") (class "Default")
      (node (ref "DA2") (pin "10") (pinfunction "Q8_10") (pintype "passive"))
    )
    (net (code "84") (name "unconnected-(DA2-Q9-Pad11)") (class "Default")
      (node (ref "DA2") (pin "11") (pinfunction "Q9_11") (pintype "passive"))
    )
    (net (code "85") (name "unconnected-(R15-Pad4)") (class "Default")
      (node (ref "R15") (pin "4") (pinfunction "4_4") (pintype "passive"))
    )
    (net (code "86") (name "unconnected-(R15-Pad8)") (class "Default")
      (node (ref "R15") (pin "8") (pinfunction "8_8") (pintype "passive"))
    )
    (net (code "87") (name "unconnected-(R20-Pad4)") (class "Default")
      (node (ref "R20") (pin "4") (pinfunction "4_4") (pintype "passive"))
    )
    (net (code "88") (name "unconnected-(R20-Pad8)") (class "Default")
      (node (ref "R20") (pin "8") (pinfunction "8_8") (pintype "passive"))
    )
    (net (code "89") (name "unconnected-(R28-Pad4)") (class "Default")
      (node (ref "R28") (pin "4") (pinfunction "4_4") (pintype "passive"))
    )
    (net (code "90") (name "unconnected-(R28-Pad8)") (class "Default")
      (node (ref "R28") (pin "8") (pinfunction "8_8") (pintype "passive"))
    )
    (net (code "91") (name "unconnected-(R33-Pad4)") (class "Default")
      (node (ref "R33") (pin "4") (pinfunction "4_4") (pintype "passive"))
    )
    (net (code "92") (name "unconnected-(R33-Pad8)") (class "Default")
      (node (ref "R33") (pin "8") (pinfunction "8_8") (pintype "passive"))
    )
  )
)
